# IO_v2.net
KiCad netlist of a schematic drawn in EAGLE
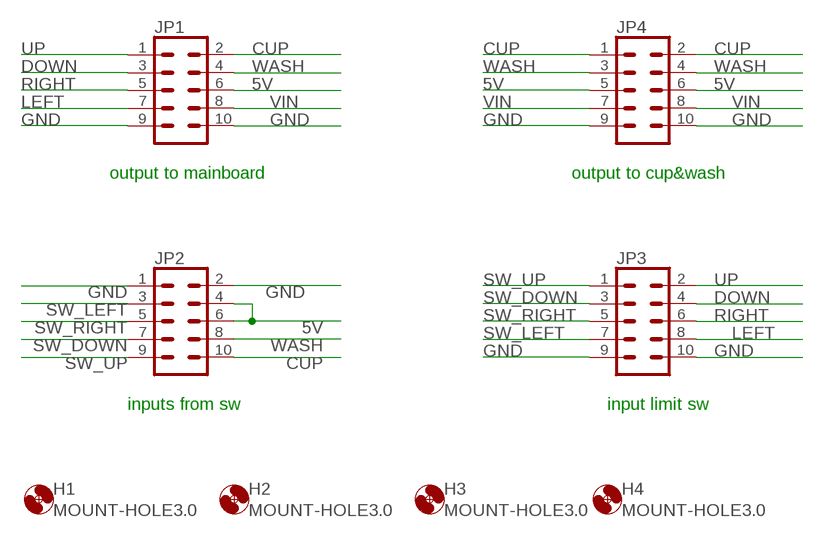
[diagram p0: schematic, sheet 1]

(export (version "E")
  (design (tool "Eeschema 10.0.6"))
  (components
    (comp (ref "H1")
      (value "MOUNT-HOLE3.0")
      (footprint "eagle-import:3,0")
      (libsource (lib "eagle-import") (part "MOUNT-HOLE3.0"))
    )
    (comp (ref "H2")
      (value "MOUNT-HOLE3.0")
      (footprint "eagle-import:3,0")
      (libsource (lib "eagle-import") (part "MOUNT-HOLE3.0"))
    )
    (comp (ref "H3")
      (value "MOUNT-HOLE3.0")
      (footprint "eagle-import:3,0")
      (libsource (lib "eagle-import") (part "MOUNT-HOLE3.0"))
    )
    (comp (ref "H4")
      (value "MOUNT-HOLE3.0")
      (footprint "eagle-import:3,0")
      (libsource (lib "eagle-import") (part "MOUNT-HOLE3.0"))
    )
    (comp (ref "JP1")
      (value "CONN_05X2PTH")
      (footprint "eagle-import:2X5")
      (libsource (lib "eagle-import") (part "CONN_05X2PTH"))
    )
    (comp (ref "JP2")
      (value "CONN_05X2PTH")
      (footprint "eagle-import:2X5")
      (libsource (lib "eagle-import") (part "CONN_05X2PTH"))
    )
    (comp (ref "JP3")
      (value "CONN_05X2PTH")
      (footprint "eagle-import:2X5")
      (libsource (lib "eagle-import") (part "CONN_05X2PTH"))
    )
    (comp (ref "JP4")
      (value "CONN_05X2PTH")
      (footprint "eagle-import:2X5")
      (libsource (lib "eagle-import") (part "CONN_05X2PTH"))
    )
  )
  (nets
    (net (code "1") (name "/5V") (class "Default")
      (node (ref "JP1") (pin "6") (pinfunction "6_6") (pintype "passive"))
      (node (ref "JP2") (pin "4") (pinfunction "4_4") (pintype "passive"))
      (node (ref "JP2") (pin "6") (pinfunction "6_6") (pintype "passive"))
      (node (ref "JP4") (pin "5") (pinfunction "5_5") (pintype "passive"))
      (node (ref "JP4") (pin "6") (pinfunction "6_6") (pintype "passive"))
    )
    (net (code "2") (name "/CUP") (class "Default")
      (node (ref "JP1") (pin "2") (pinfunction "2_2") (pintype "passive"))
      (node (ref "JP2") (pin "10") (pinfunction "10_10") (pintype "passive"))
      (node (ref "JP4") (pin "1") (pinfunction "1_1") (pintype "passive"))
      (node (ref "JP4") (pin "2") (pinfunction "2_2") (pintype "passive"))
    )
    (net (code "3") (name "/DOWN") (class "Default")
      (node (ref "JP1") (pin "3") (pinfunction "3_3") (pintype "passive"))
      (node (ref "JP3") (pin "4") (pinfunction "4_4") (pintype "passive"))
    )
    (net (code "4") (name "/GND") (class "Default")
      (node (ref "JP1") (pin "10") (pinfunction "10_10") (pintype "passive"))
      (node (ref "JP1") (pin "9") (pinfunction "9_9") (pintype "passive"))
      (node (ref "JP2") (pin "1") (pinfunction "1_1") (pintype "passive"))
      (node (ref "JP2") (pin "2") (pinfunction "2_2") (pintype "passive"))
      (node (ref "JP3") (pin "10") (pinfunction "10_10") (pintype "passive"))
      (node (ref "JP3") (pin "9") (pinfunction "9_9") (pintype "passive"))
      (node (ref "JP4") (pin "10") (pinfunction "10_10") (pintype "passive"))
      (node (ref "JP4") (pin "9") (pinfunction "9_9") (pintype "passive"))
    )
    (net (code "5") (name "/LEFT") (class "Default")
      (node (ref "JP1") (pin "7") (pinfunction "7_7") (pintype "passive"))
      (node (ref "JP3") (pin "8") (pinfunction "8_8") (pintype "passive"))
    )
    (net (code "6") (name "/RIGHT") (class "Default")
      (node (ref "JP1") (pin "5") (pinfunction "5_5") (pintype "passive"))
      (node (ref "JP3") (pin "6") (pinfunction "6_6") (pintype "passive"))
    )
    (net (code "7") (name "/SW_DOWN") (class "Default")
      (node (ref "JP2") (pin "7") (pinfunction "7_7") (pintype "passive"))
      (node (ref "JP3") (pin "3") (pinfunction "3_3") (pintype "passive"))
    )
    (net (code "8") (name "/SW_LEFT") (class "Default")
      (node (ref "JP2") (pin "3") (pinfunction "3_3") (pintype "passive"))
      (node (ref "JP3") (pin "7") (pinfunction "7_7") (pintype "passive"))
    )
    (net (code "9") (name "/SW_RIGHT") (class "Default")
      (node (ref "JP2") (pin "5") (pinfunction "5_5") (pintype "passive"))
      (node (ref "JP3") (pin "5") (pinfunction "5_5") (pintype "passive"))
    )
    (net (code "10") (name "/SW_UP") (class "Default")
      (node (ref "JP2") (pin "9") (pinfunction "9_9") (pintype "passive"))
      (node (ref "JP3") (pin "1") (pinfunction "1_1") (pintype "passive"))
    )
    (net (code "11") (name "/UP") (class "Default")
      (node (ref "JP1") (pin "1") (pinfunction "1_1") (pintype "passive"))
      (node (ref "JP3") (pin "2") (pinfunction "2_2") (pintype "passive"))
    )
    (net (code "12") (name "/VIN") (class "Default")
      (node (ref "JP1") (pin "8") (pinfunction "8_8") (pintype "passive"))
      (node (ref "JP4") (pin "7") (pinfunction "7_7") (pintype "passive"))
      (node (ref "JP4") (pin "8") (pinfunction "8_8") (pintype "passive"))
    )
    (net (code "13") (name "/WASH") (class "Default")
      (node (ref "JP1") (pin "4") (pinfunction "4_4") (pintype "passive"))
      (node (ref "JP2") (pin "8") (pinfunction "8_8") (pintype "passive"))
      (node (ref "JP4") (pin "3") (pinfunction "3_3") (pintype "passive"))
      (node (ref "JP4") (pin "4") (pinfunction "4_4") (pintype "passive"))
    )
  )
)
